# schema_rs232_MAX3232.net
KiCad netlist of a schematic drawn in EAGLE
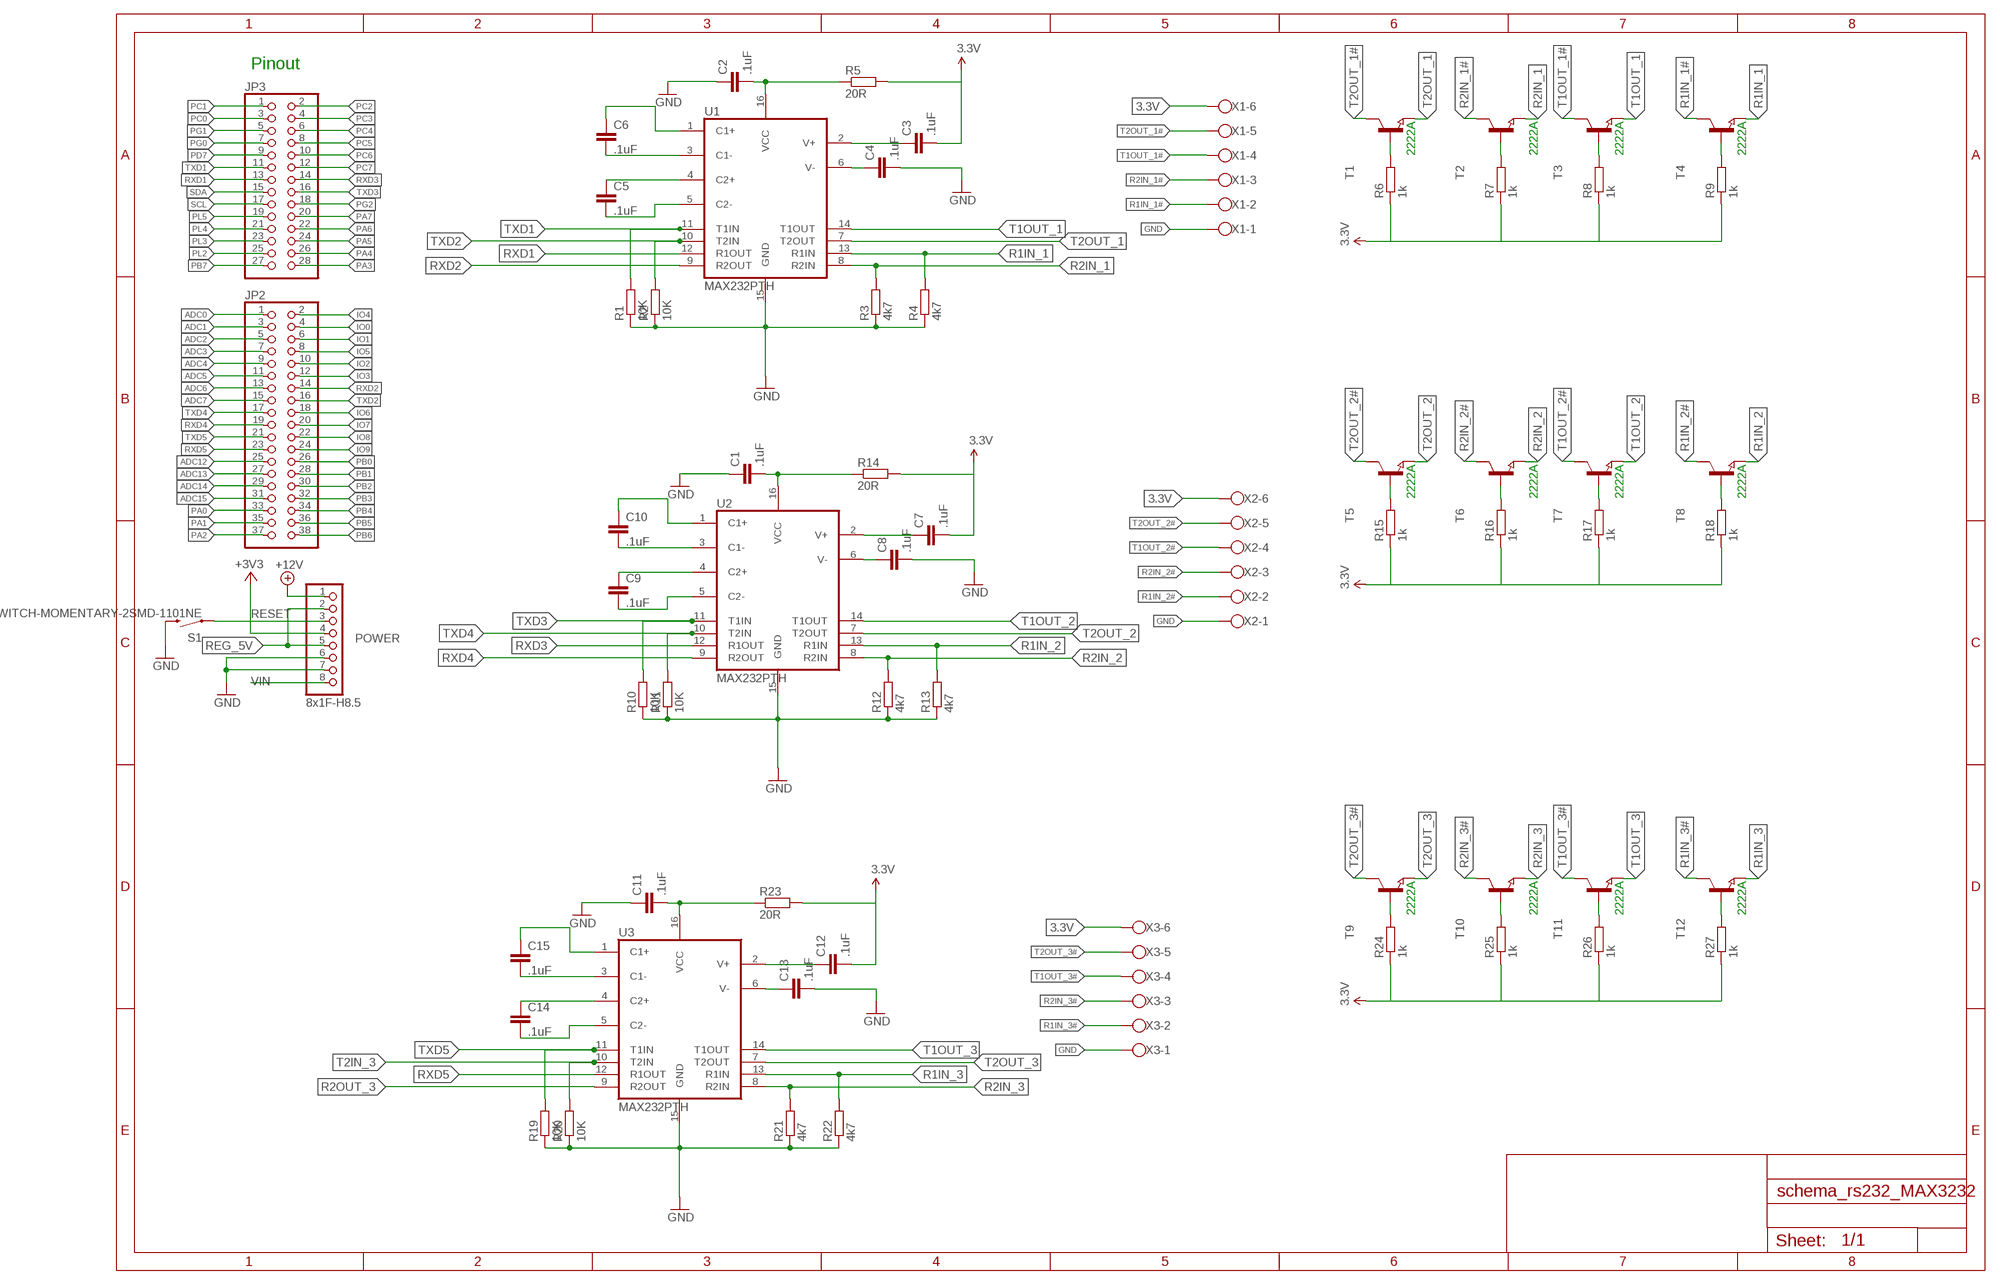
[diagram p0: schematic, sheet 1]

(export (version "E")
  (design (tool "Eeschema 10.0.6"))
  (components
    (comp (ref "C1")
      (value ".1uF")
      (footprint "eagle-import:C0805")
      (libsource (lib "eagle-import") (part "C-EUC0805"))
    )
    (comp (ref "C2")
      (value ".1uF")
      (footprint "eagle-import:C0805")
      (libsource (lib "eagle-import") (part "C-EUC0805"))
    )
    (comp (ref "C3")
      (value ".1uF")
      (footprint "eagle-import:C0805")
      (libsource (lib "eagle-import") (part "C-EUC0805"))
    )
    (comp (ref "C4")
      (value ".1uF")
      (footprint "eagle-import:C0805")
      (libsource (lib "eagle-import") (part "C-EUC0805"))
    )
    (comp (ref "C5")
      (value ".1uF")
      (footprint "eagle-import:C0805")
      (libsource (lib "eagle-import") (part "C-EUC0805"))
    )
    (comp (ref "C6")
      (value ".1uF")
      (footprint "eagle-import:C0805")
      (libsource (lib "eagle-import") (part "C-EUC0805"))
    )
    (comp (ref "C7")
      (value ".1uF")
      (footprint "eagle-import:C0805")
      (libsource (lib "eagle-import") (part "C-EUC0805"))
    )
    (comp (ref "C8")
      (value ".1uF")
      (footprint "eagle-import:C0805")
      (libsource (lib "eagle-import") (part "C-EUC0805"))
    )
    (comp (ref "C9")
      (value ".1uF")
      (footprint "eagle-import:C0805")
      (libsource (lib "eagle-import") (part "C-EUC0805"))
    )
    (comp (ref "C10")
      (value ".1uF")
      (footprint "eagle-import:C0805")
      (libsource (lib "eagle-import") (part "C-EUC0805"))
    )
    (comp (ref "C11")
      (value ".1uF")
      (footprint "eagle-import:C0805")
      (libsource (lib "eagle-import") (part "C-EUC0805"))
    )
    (comp (ref "C12")
      (value ".1uF")
      (footprint "eagle-import:C0805")
      (libsource (lib "eagle-import") (part "C-EUC0805"))
    )
    (comp (ref "C13")
      (value ".1uF")
      (footprint "eagle-import:C0805")
      (libsource (lib "eagle-import") (part "C-EUC0805"))
    )
    (comp (ref "C14")
      (value ".1uF")
      (footprint "eagle-import:C0805")
      (libsource (lib "eagle-import") (part "C-EUC0805"))
    )
    (comp (ref "C15")
      (value ".1uF")
      (footprint "eagle-import:C0805")
      (libsource (lib "eagle-import") (part "C-EUC0805"))
    )
    (comp (ref "JP2")
      (value "PINHD-2X19")
      (footprint "eagle-import:2X19")
      (libsource (lib "eagle-import") (part "PINHD-2X19"))
    )
    (comp (ref "JP3")
      (value "PINHD-2X14")
      (footprint "eagle-import:2X14")
      (libsource (lib "eagle-import") (part "PINHD-2X14"))
    )
    (comp (ref "POWER")
      (value "8x1F-H8.5")
      (footprint "eagle-import:1X08")
      (libsource (lib "eagle-import") (part "PINHD-1X8"))
    )
    (comp (ref "R1")
      (value "10K")
      (footprint "eagle-import:R0805")
      (libsource (lib "eagle-import") (part "R-EU_R0805"))
    )
    (comp (ref "R2")
      (value "10K")
      (footprint "eagle-import:R0805")
      (libsource (lib "eagle-import") (part "R-EU_R0805"))
    )
    (comp (ref "R3")
      (value "4k7")
      (footprint "eagle-import:R0805")
      (libsource (lib "eagle-import") (part "R-EU_R0805"))
    )
    (comp (ref "R4")
      (value "4k7")
      (footprint "eagle-import:R0805")
      (libsource (lib "eagle-import") (part "R-EU_R0805"))
    )
    (comp (ref "R5")
      (value "20R")
      (footprint "eagle-import:R0805")
      (libsource (lib "eagle-import") (part "R-EU_R0805"))
    )
    (comp (ref "R6")
      (value "1k")
      (footprint "eagle-import:R0805")
      (libsource (lib "eagle-import") (part "R-EU_R0805"))
    )
    (comp (ref "R7")
      (value "1k")
      (footprint "eagle-import:R0805")
      (libsource (lib "eagle-import") (part "R-EU_R0805"))
    )
    (comp (ref "R8")
      (value "1k")
      (footprint "eagle-import:R0805")
      (libsource (lib "eagle-import") (part "R-EU_R0805"))
    )
    (comp (ref "R9")
      (value "1k")
      (footprint "eagle-import:R0805")
      (libsource (lib "eagle-import") (part "R-EU_R0805"))
    )
    (comp (ref "R10")
      (value "10K")
      (footprint "eagle-import:R0805")
      (libsource (lib "eagle-import") (part "R-EU_R0805"))
    )
    (comp (ref "R11")
      (value "10K")
      (footprint "eagle-import:R0805")
      (libsource (lib "eagle-import") (part "R-EU_R0805"))
    )
    (comp (ref "R12")
      (value "4k7")
      (footprint "eagle-import:R0805")
      (libsource (lib "eagle-import") (part "R-EU_R0805"))
    )
    (comp (ref "R13")
      (value "4k7")
      (footprint "eagle-import:R0805")
      (libsource (lib "eagle-import") (part "R-EU_R0805"))
    )
    (comp (ref "R14")
      (value "20R")
      (footprint "eagle-import:R0805")
      (libsource (lib "eagle-import") (part "R-EU_R0805"))
    )
    (comp (ref "R15")
      (value "1k")
      (footprint "eagle-import:R0805")
      (libsource (lib "eagle-import") (part "R-EU_R0805"))
    )
    (comp (ref "R16")
      (value "1k")
      (footprint "eagle-import:R0805")
      (libsource (lib "eagle-import") (part "R-EU_R0805"))
    )
    (comp (ref "R17")
      (value "1k")
      (footprint "eagle-import:R0805")
      (libsource (lib "eagle-import") (part "R-EU_R0805"))
    )
    (comp (ref "R18")
      (value "1k")
      (footprint "eagle-import:R0805")
      (libsource (lib "eagle-import") (part "R-EU_R0805"))
    )
    (comp (ref "R19")
      (value "10K")
      (footprint "eagle-import:R0805")
      (libsource (lib "eagle-import") (part "R-EU_R0805"))
    )
    (comp (ref "R20")
      (value "10K")
      (footprint "eagle-import:R0805")
      (libsource (lib "eagle-import") (part "R-EU_R0805"))
    )
    (comp (ref "R21")
      (value "4k7")
      (footprint "eagle-import:R0805")
      (libsource (lib "eagle-import") (part "R-EU_R0805"))
    )
    (comp (ref "R22")
      (value "4k7")
      (footprint "eagle-import:R0805")
      (libsource (lib "eagle-import") (part "R-EU_R0805"))
    )
    (comp (ref "R23")
      (value "20R")
      (footprint "eagle-import:R0805")
      (libsource (lib "eagle-import") (part "R-EU_R0805"))
    )
    (comp (ref "R24")
      (value "1k")
      (footprint "eagle-import:R0805")
      (libsource (lib "eagle-import") (part "R-EU_R0805"))
    )
    (comp (ref "R25")
      (value "1k")
      (footprint "eagle-import:R0805")
      (libsource (lib "eagle-import") (part "R-EU_R0805"))
    )
    (comp (ref "R26")
      (value "1k")
      (footprint "eagle-import:R0805")
      (libsource (lib "eagle-import") (part "R-EU_R0805"))
    )
    (comp (ref "R27")
      (value "1k")
      (footprint "eagle-import:R0805")
      (libsource (lib "eagle-import") (part "R-EU_R0805"))
    )
    (comp (ref "S1")
      (value "SWITCH-MOMENTARY-2SMD-1101NE")
      (footprint "eagle-import:TACTILE-SWITCH-1101NE")
      (libsource (lib "eagle-import") (part "SWITCH-MOMENTARY-2SMD-1101NE"))
    )
    (comp (ref "T1")
      (value "NPN-TRANSISTOR_SOT23")
      (footprint "eagle-import:SOT23")
      (libsource (lib "eagle-import") (part "NPN-TRANSISTOR_SOT23"))
    )
    (comp (ref "T2")
      (value "NPN-TRANSISTOR_SOT23")
      (footprint "eagle-import:SOT23")
      (libsource (lib "eagle-import") (part "NPN-TRANSISTOR_SOT23"))
    )
    (comp (ref "T3")
      (value "NPN-TRANSISTOR_SOT23")
      (footprint "eagle-import:SOT23")
      (libsource (lib "eagle-import") (part "NPN-TRANSISTOR_SOT23"))
    )
    (comp (ref "T4")
      (value "NPN-TRANSISTOR_SOT23")
      (footprint "eagle-import:SOT23")
      (libsource (lib "eagle-import") (part "NPN-TRANSISTOR_SOT23"))
    )
    (comp (ref "T5")
      (value "NPN-TRANSISTOR_SOT23")
      (footprint "eagle-import:SOT23")
      (libsource (lib "eagle-import") (part "NPN-TRANSISTOR_SOT23"))
    )
    (comp (ref "T6")
      (value "NPN-TRANSISTOR_SOT23")
      (footprint "eagle-import:SOT23")
      (libsource (lib "eagle-import") (part "NPN-TRANSISTOR_SOT23"))
    )
    (comp (ref "T7")
      (value "NPN-TRANSISTOR_SOT23")
      (footprint "eagle-import:SOT23")
      (libsource (lib "eagle-import") (part "NPN-TRANSISTOR_SOT23"))
    )
    (comp (ref "T8")
      (value "NPN-TRANSISTOR_SOT23")
      (footprint "eagle-import:SOT23")
      (libsource (lib "eagle-import") (part "NPN-TRANSISTOR_SOT23"))
    )
    (comp (ref "T9")
      (value "NPN-TRANSISTOR_SOT23")
      (footprint "eagle-import:SOT23")
      (libsource (lib "eagle-import") (part "NPN-TRANSISTOR_SOT23"))
    )
    (comp (ref "T10")
      (value "NPN-TRANSISTOR_SOT23")
      (footprint "eagle-import:SOT23")
      (libsource (lib "eagle-import") (part "NPN-TRANSISTOR_SOT23"))
    )
    (comp (ref "T11")
      (value "NPN-TRANSISTOR_SOT23")
      (footprint "eagle-import:SOT23")
      (libsource (lib "eagle-import") (part "NPN-TRANSISTOR_SOT23"))
    )
    (comp (ref "T12")
      (value "NPN-TRANSISTOR_SOT23")
      (footprint "eagle-import:SOT23")
      (libsource (lib "eagle-import") (part "NPN-TRANSISTOR_SOT23"))
    )
    (comp (ref "U1")
      (value "MAX232PTH")
      (footprint "eagle-import:DIL16")
      (libsource (lib "eagle-import") (part "MAX232PTH"))
    )
    (comp (ref "U2")
      (value "MAX232PTH")
      (footprint "eagle-import:DIL16")
      (libsource (lib "eagle-import") (part "MAX232PTH"))
    )
    (comp (ref "U3")
      (value "MAX232PTH")
      (footprint "eagle-import:DIL16")
      (libsource (lib "eagle-import") (part "MAX232PTH"))
    )
    (comp (ref "X1")
      (value "W237-6")
      (footprint "eagle-import:W237-6")
      (libsource (lib "eagle-import") (part "W237-6"))
    )
    (comp (ref "X2")
      (value "W237-6")
      (footprint "eagle-import:W237-6")
      (libsource (lib "eagle-import") (part "W237-6"))
    )
    (comp (ref "X3")
      (value "W237-6")
      (footprint "eagle-import:W237-6")
      (libsource (lib "eagle-import") (part "W237-6"))
    )
  )
  (nets
    (net (code "1") (name "+12V") (class "Default")
      (node (ref "POWER") (pin "1") (pinfunction "1_1") (pintype "passive"))
    )
    (net (code "2") (name "/RESET") (class "Default")
      (node (ref "POWER") (pin "3") (pinfunction "3_3") (pintype "passive"))
      (node (ref "S1") (pin "1") (pinfunction "1_1") (pintype "passive"))
    )
    (net (code "3") (name "/VIN") (class "Default")
      (node (ref "POWER") (pin "8") (pinfunction "8_8") (pintype "passive"))
    )
    (net (code "4") (name "3.3V") (class "Default")
      (node (ref "C12") (pin "2") (pinfunction "2_2") (pintype "passive"))
      (node (ref "C3") (pin "2") (pinfunction "2_2") (pintype "passive"))
      (node (ref "C7") (pin "2") (pinfunction "2_2") (pintype "passive"))
      (node (ref "POWER") (pin "4") (pinfunction "4_4") (pintype "passive"))
      (node (ref "R14") (pin "2") (pinfunction "2_2") (pintype "passive"))
      (node (ref "R15") (pin "1") (pinfunction "1_1") (pintype "passive"))
      (node (ref "R16") (pin "1") (pinfunction "1_1") (pintype "passive"))
      (node (ref "R17") (pin "1") (pinfunction "1_1") (pintype "passive"))
      (node (ref "R18") (pin "1") (pinfunction "1_1") (pintype "passive"))
      (node (ref "R23") (pin "2") (pinfunction "2_2") (pintype "passive"))
      (node (ref "R24") (pin "1") (pinfunction "1_1") (pintype "passive"))
      (node (ref "R25") (pin "1") (pinfunction "1_1") (pintype "passive"))
      (node (ref "R26") (pin "1") (pinfunction "1_1") (pintype "passive"))
      (node (ref "R27") (pin "1") (pinfunction "1_1") (pintype "passive"))
      (node (ref "R5") (pin "2") (pinfunction "2_2") (pintype "passive"))
      (node (ref "R6") (pin "1") (pinfunction "1_1") (pintype "passive"))
      (node (ref "R7") (pin "1") (pinfunction "1_1") (pintype "passive"))
      (node (ref "R8") (pin "1") (pinfunction "1_1") (pintype "passive"))
      (node (ref "R9") (pin "1") (pinfunction "1_1") (pintype "passive"))
      (node (ref "X1") (pin "6") (pinfunction "KL_6") (pintype "passive"))
      (node (ref "X2") (pin "6") (pinfunction "KL_6") (pintype "passive"))
      (node (ref "X3") (pin "6") (pinfunction "KL_6") (pintype "passive"))
    )
    (net (code "5") (name "ADC0") (class "Default")
      (node (ref "JP2") (pin "1") (pinfunction "1_1") (pintype "passive"))
    )
    (net (code "6") (name "ADC1") (class "Default")
      (node (ref "JP2") (pin "3") (pinfunction "3_3") (pintype "passive"))
    )
    (net (code "7") (name "ADC2") (class "Default")
      (node (ref "JP2") (pin "5") (pinfunction "5_5") (pintype "passive"))
    )
    (net (code "8") (name "ADC3") (class "Default")
      (node (ref "JP2") (pin "7") (pinfunction "7_7") (pintype "passive"))
    )
    (net (code "9") (name "ADC4") (class "Default")
      (node (ref "JP2") (pin "9") (pinfunction "9_9") (pintype "passive"))
    )
    (net (code "10") (name "ADC5") (class "Default")
      (node (ref "JP2") (pin "11") (pinfunction "11_11") (pintype "passive"))
    )
    (net (code "11") (name "ADC6") (class "Default")
      (node (ref "JP2") (pin "13") (pinfunction "13_13") (pintype "passive"))
    )
    (net (code "12") (name "ADC7") (class "Default")
      (node (ref "JP2") (pin "15") (pinfunction "15_15") (pintype "passive"))
    )
    (net (code "13") (name "ADC12") (class "Default")
      (node (ref "JP2") (pin "25") (pinfunction "25_25") (pintype "passive"))
    )
    (net (code "14") (name "ADC13") (class "Default")
      (node (ref "JP2") (pin "27") (pinfunction "27_27") (pintype "passive"))
    )
    (net (code "15") (name "ADC14") (class "Default")
      (node (ref "JP2") (pin "29") (pinfunction "29_29") (pintype "passive"))
    )
    (net (code "16") (name "ADC15") (class "Default")
      (node (ref "JP2") (pin "31") (pinfunction "31_31") (pintype "passive"))
    )
    (net (code "17") (name "GND") (class "Default")
      (node (ref "C1") (pin "1") (pinfunction "1_1") (pintype "passive"))
      (node (ref "C11") (pin "1") (pinfunction "1_1") (pintype "passive"))
      (node (ref "C13") (pin "2") (pinfunction "2_2") (pintype "passive"))
      (node (ref "C2") (pin "1") (pinfunction "1_1") (pintype "passive"))
      (node (ref "C4") (pin "2") (pinfunction "2_2") (pintype "passive"))
      (node (ref "C8") (pin "2") (pinfunction "2_2") (pintype "passive"))
      (node (ref "POWER") (pin "6") (pinfunction "6_6") (pintype "passive"))
      (node (ref "POWER") (pin "7") (pinfunction "7_7") (pintype "passive"))
      (node (ref "R1") (pin "1") (pinfunction "1_1") (pintype "passive"))
      (node (ref "R10") (pin "1") (pinfunction "1_1") (pintype "passive"))
      (node (ref "R11") (pin "1") (pinfunction "1_1") (pintype "passive"))
      (node (ref "R12") (pin "1") (pinfunction "1_1") (pintype "passive"))
      (node (ref "R13") (pin "1") (pinfunction "1_1") (pintype "passive"))
      (node (ref "R19") (pin "1") (pinfunction "1_1") (pintype "passive"))
      (node (ref "R2") (pin "1") (pinfunction "1_1") (pintype "passive"))
      (node (ref "R20") (pin "1") (pinfunction "1_1") (pintype "passive"))
      (node (ref "R21") (pin "1") (pinfunction "1_1") (pintype "passive"))
      (node (ref "R22") (pin "1") (pinfunction "1_1") (pintype "passive"))
      (node (ref "R3") (pin "1") (pinfunction "1_1") (pintype "passive"))
      (node (ref "R4") (pin "1") (pinfunction "1_1") (pintype "passive"))
      (node (ref "S1") (pin "2") (pinfunction "2_2") (pintype "passive"))
      (node (ref "U1") (pin "15") (pinfunction "GND_15") (pintype "bidirectional"))
      (node (ref "U2") (pin "15") (pinfunction "GND_15") (pintype "bidirectional"))
      (node (ref "U3") (pin "15") (pinfunction "GND_15") (pintype "bidirectional"))
      (node (ref "X1") (pin "1") (pinfunction "KL_1") (pintype "passive"))
      (node (ref "X2") (pin "1") (pinfunction "KL_1") (pintype "passive"))
      (node (ref "X3") (pin "1") (pinfunction "KL_1") (pintype "passive"))
    )
    (net (code "18") (name "IO0") (class "Default")
      (node (ref "JP2") (pin "4") (pinfunction "4_4") (pintype "passive"))
    )
    (net (code "19") (name "IO1") (class "Default")
      (node (ref "JP2") (pin "6") (pinfunction "6_6") (pintype "passive"))
    )
    (net (code "20") (name "IO2") (class "Default")
      (node (ref "JP2") (pin "10") (pinfunction "10_10") (pintype "passive"))
    )
    (net (code "21") (name "IO3") (class "Default")
      (node (ref "JP2") (pin "12") (pinfunction "12_12") (pintype "passive"))
    )
    (net (code "22") (name "IO4") (class "Default")
      (node (ref "JP2") (pin "2") (pinfunction "2_2") (pintype "passive"))
    )
    (net (code "23") (name "IO5") (class "Default")
      (node (ref "JP2") (pin "8") (pinfunction "8_8") (pintype "passive"))
    )
    (net (code "24") (name "IO6") (class "Default")
      (node (ref "JP2") (pin "18") (pinfunction "18_18") (pintype "passive"))
    )
    (net (code "25") (name "IO7") (class "Default")
      (node (ref "JP2") (pin "20") (pinfunction "20_20") (pintype "passive"))
    )
    (net (code "26") (name "IO8") (class "Default")
      (node (ref "JP2") (pin "22") (pinfunction "22_22") (pintype "passive"))
    )
    (net (code "27") (name "IO9") (class "Default")
      (node (ref "JP2") (pin "24") (pinfunction "24_24") (pintype "passive"))
    )
    (net (code "28") (name "Net-(T1-B)") (class "Default")
      (node (ref "R6") (pin "2") (pinfunction "2_2") (pintype "passive"))
      (node (ref "T1") (pin "1") (pinfunction "B_1") (pintype "passive"))
    )
    (net (code "29") (name "Net-(T2-B)") (class "Default")
      (node (ref "R7") (pin "2") (pinfunction "2_2") (pintype "passive"))
      (node (ref "T2") (pin "1") (pinfunction "B_1") (pintype "passive"))
    )
    (net (code "30") (name "Net-(T3-B)") (class "Default")
      (node (ref "R8") (pin "2") (pinfunction "2_2") (pintype "passive"))
      (node (ref "T3") (pin "1") (pinfunction "B_1") (pintype "passive"))
    )
    (net (code "31") (name "Net-(T4-B)") (class "Default")
      (node (ref "R9") (pin "2") (pinfunction "2_2") (pintype "passive"))
      (node (ref "T4") (pin "1") (pinfunction "B_1") (pintype "passive"))
    )
    (net (code "32") (name "Net-(T5-B)") (class "Default")
      (node (ref "R15") (pin "2") (pinfunction "2_2") (pintype "passive"))
      (node (ref "T5") (pin "1") (pinfunction "B_1") (pintype "passive"))
    )
    (net (code "33") (name "Net-(T6-B)") (class "Default")
      (node (ref "R16") (pin "2") (pinfunction "2_2") (pintype "passive"))
      (node (ref "T6") (pin "1") (pinfunction "B_1") (pintype "passive"))
    )
    (net (code "34") (name "Net-(T7-B)") (class "Default")
      (node (ref "R17") (pin "2") (pinfunction "2_2") (pintype "passive"))
      (node (ref "T7") (pin "1") (pinfunction "B_1") (pintype "passive"))
    )
    (net (code "35") (name "Net-(T8-B)") (class "Default")
      (node (ref "R18") (pin "2") (pinfunction "2_2") (pintype "passive"))
      (node (ref "T8") (pin "1") (pinfunction "B_1") (pintype "passive"))
    )
    (net (code "36") (name "Net-(T9-B)") (class "Default")
      (node (ref "R24") (pin "2") (pinfunction "2_2") (pintype "passive"))
      (node (ref "T9") (pin "1") (pinfunction "B_1") (pintype "passive"))
    )
    (net (code "37") (name "Net-(T10-B)") (class "Default")
      (node (ref "R25") (pin "2") (pinfunction "2_2") (pintype "passive"))
      (node (ref "T10") (pin "1") (pinfunction "B_1") (pintype "passive"))
    )
    (net (code "38") (name "Net-(T11-B)") (class "Default")
      (node (ref "R26") (pin "2") (pinfunction "2_2") (pintype "passive"))
      (node (ref "T11") (pin "1") (pinfunction "B_1") (pintype "passive"))
    )
    (net (code "39") (name "Net-(T12-B)") (class "Default")
      (node (ref "R27") (pin "2") (pinfunction "2_2") (pintype "passive"))
      (node (ref "T12") (pin "1") (pinfunction "B_1") (pintype "passive"))
    )
    (net (code "40") (name "Net-(U1-C1+)") (class "Default")
      (node (ref "C6") (pin "1") (pinfunction "1_1") (pintype "passive"))
      (node (ref "U1") (pin "1") (pinfunction "C1+_1") (pintype "bidirectional"))
    )
    (net (code "41") (name "Net-(U1-C1-)") (class "Default")
      (node (ref "C6") (pin "2") (pinfunction "2_2") (pintype "passive"))
      (node (ref "U1") (pin "3") (pinfunction "C1-_3") (pintype "bidirectional"))
    )
    (net (code "42") (name "Net-(U1-C2+)") (class "Default")
      (node (ref "C5") (pin "1") (pinfunction "1_1") (pintype "passive"))
      (node (ref "U1") (pin "4") (pinfunction "C2+_4") (pintype "bidirectional"))
    )
    (net (code "43") (name "Net-(U1-C2-)") (class "Default")
      (node (ref "C5") (pin "2") (pinfunction "2_2") (pintype "passive"))
      (node (ref "U1") (pin "5") (pinfunction "C2-_5") (pintype "bidirectional"))
    )
    (net (code "44") (name "Net-(U1-V+)") (class "Default")
      (node (ref "C3") (pin "1") (pinfunction "1_1") (pintype "passive"))
      (node (ref "U1") (pin "2") (pinfunction "V+_2") (pintype "bidirectional"))
    )
    (net (code "45") (name "Net-(U1-V-)") (class "Default")
      (node (ref "C4") (pin "1") (pinfunction "1_1") (pintype "passive"))
      (node (ref "U1") (pin "6") (pinfunction "V-_6") (pintype "bidirectional"))
    )
    (net (code "46") (name "Net-(U1-VCC)") (class "Default")
      (node (ref "C2") (pin "2") (pinfunction "2_2") (pintype "passive"))
      (node (ref "R5") (pin "1") (pinfunction "1_1") (pintype "passive"))
      (node (ref "U1") (pin "16") (pinfunction "VCC_16") (pintype "bidirectional"))
    )
    (net (code "47") (name "Net-(U2-C1+)") (class "Default")
      (node (ref "C10") (pin "1") (pinfunction "1_1") (pintype "passive"))
      (node (ref "U2") (pin "1") (pinfunction "C1+_1") (pintype "bidirectional"))
    )
    (net (code "48") (name "Net-(U2-C1-)") (class "Default")
      (node (ref "C10") (pin "2") (pinfunction "2_2") (pintype "passive"))
      (node (ref "U2") (pin "3") (pinfunction "C1-_3") (pintype "bidirectional"))
    )
    (net (code "49") (name "Net-(U2-C2+)") (class "Default")
      (node (ref "C9") (pin "1") (pinfunction "1_1") (pintype "passive"))
      (node (ref "U2") (pin "4") (pinfunction "C2+_4") (pintype "bidirectional"))
    )
    (net (code "50") (name "Net-(U2-C2-)") (class "Default")
      (node (ref "C9") (pin "2") (pinfunction "2_2") (pintype "passive"))
      (node (ref "U2") (pin "5") (pinfunction "C2-_5") (pintype "bidirectional"))
    )
    (net (code "51") (name "Net-(U2-V+)") (class "Default")
      (node (ref "C7") (pin "1") (pinfunction "1_1") (pintype "passive"))
      (node (ref "U2") (pin "2") (pinfunction "V+_2") (pintype "bidirectional"))
    )
    (net (code "52") (name "Net-(U2-V-)") (class "Default")
      (node (ref "C8") (pin "1") (pinfunction "1_1") (pintype "passive"))
      (node (ref "U2") (pin "6") (pinfunction "V-_6") (pintype "bidirectional"))
    )
    (net (code "53") (name "Net-(U2-VCC)") (class "Default")
      (node (ref "C1") (pin "2") (pinfunction "2_2") (pintype "passive"))
      (node (ref "R14") (pin "1") (pinfunction "1_1") (pintype "passive"))
      (node (ref "U2") (pin "16") (pinfunction "VCC_16") (pintype "bidirectional"))
    )
    (net (code "54") (name "Net-(U3-C1+)") (class "Default")
      (node (ref "C15") (pin "1") (pinfunction "1_1") (pintype "passive"))
      (node (ref "U3") (pin "1") (pinfunction "C1+_1") (pintype "bidirectional"))
    )
    (net (code "55") (name "Net-(U3-C1-)") (class "Default")
      (node (ref "C15") (pin "2") (pinfunction "2_2") (pintype "passive"))
      (node (ref "U3") (pin "3") (pinfunction "C1-_3") (pintype "bidirectional"))
    )
    (net (code "56") (name "Net-(U3-C2+)") (class "Default")
      (node (ref "C14") (pin "1") (pinfunction "1_1") (pintype "passive"))
      (node (ref "U3") (pin "4") (pinfunction "C2+_4") (pintype "bidirectional"))
    )
    (net (code "57") (name "Net-(U3-C2-)") (class "Default")
      (node (ref "C14") (pin "2") (pinfunction "2_2") (pintype "passive"))
      (node (ref "U3") (pin "5") (pinfunction "C2-_5") (pintype "bidirectional"))
    )
    (net (code "58") (name "Net-(U3-V+)") (class "Default")
      (node (ref "C12") (pin "1") (pinfunction "1_1") (pintype "passive"))
      (node (ref "U3") (pin "2") (pinfunction "V+_2") (pintype "bidirectional"))
    )
    (net (code "59") (name "Net-(U3-V-)") (class "Default")
      (node (ref "C13") (pin "1") (pinfunction "1_1") (pintype "passive"))
      (node (ref "U3") (pin "6") (pinfunction "V-_6") (pintype "bidirectional"))
    )
    (net (code "60") (name "Net-(U3-VCC)") (class "Default")
      (node (ref "C11") (pin "2") (pinfunction "2_2") (pintype "passive"))
      (node (ref "R23") (pin "1") (pinfunction "1_1") (pintype "passive"))
      (node (ref "U3") (pin "16") (pinfunction "VCC_16") (pintype "bidirectional"))
    )
    (net (code "61") (name "PA0") (class "Default")
      (node (ref "JP2") (pin "33") (pinfunction "33_33") (pintype "passive"))
    )
    (net (code "62") (name "PA1") (class "Default")
      (node (ref "JP2") (pin "35") (pinfunction "35_35") (pintype "passive"))
    )
    (net (code "63") (name "PA2") (class "Default")
      (node (ref "JP2") (pin "37") (pinfunction "37_37") (pintype "passive"))
    )
    (net (code "64") (name "PA3") (class "Default")
      (node (ref "JP3") (pin "28") (pinfunction "28_28") (pintype "passive"))
    )
    (net (code "65") (name "PA4") (class "Default")
      (node (ref "JP3") (pin "26") (pinfunction "26_26") (pintype "passive"))
    )
    (net (code "66") (name "PA5") (class "Default")
      (node (ref "JP3") (pin "24") (pinfunction "24_24") (pintype "passive"))
    )
    (net (code "67") (name "PA6") (class "Default")
      (node (ref "JP3") (pin "22") (pinfunction "22_22") (pintype "passive"))
    )
    (net (code "68") (name "PA7") (class "Default")
      (node (ref "JP3") (pin "20") (pinfunction "20_20") (pintype "passive"))
    )
    (net (code "69") (name "PB0") (class "Default")
      (node (ref "JP2") (pin "26") (pinfunction "26_26") (pintype "passive"))
    )
    (net (code "70") (name "PB1") (class "Default")
      (node (ref "JP2") (pin "28") (pinfunction "28_28") (pintype "passive"))
    )
    (net (code "71") (name "PB2") (class "Default")
      (node (ref "JP2") (pin "30") (pinfunction "30_30") (pintype "passive"))
    )
    (net (code "72") (name "PB3") (class "Default")
      (node (ref "JP2") (pin "32") (pinfunction "32_32") (pintype "passive"))
    )
    (net (code "73") (name "PB4") (class "Default")
      (node (ref "JP2") (pin "34") (pinfunction "34_34") (pintype "passive"))
    )
    (net (code "74") (name "PB5") (class "Default")
      (node (ref "JP2") (pin "36") (pinfunction "36_36") (pintype "passive"))
    )
    (net (code "75") (name "PB6") (class "Default")
      (node (ref "JP2") (pin "38") (pinfunction "38_38") (pintype "passive"))
    )
    (net (code "76") (name "PB7") (class "Default")
      (node (ref "JP3") (pin "27") (pinfunction "27_27") (pintype "passive"))
    )
    (net (code "77") (name "PC0") (class "Default")
      (node (ref "JP3") (pin "3") (pinfunction "3_3") (pintype "passive"))
    )
    (net (code "78") (name "PC1") (class "Default")
      (node (ref "JP3") (pin "1") (pinfunction "1_1") (pintype "passive"))
    )
    (net (code "79") (name "PC2") (class "Default")
      (node (ref "JP3") (pin "2") (pinfunction "2_2") (pintype "passive"))
    )
    (net (code "80") (name "PC3") (class "Default")
      (node (ref "JP3") (pin "4") (pinfunction "4_4") (pintype "passive"))
    )
    (net (code "81") (name "PC4") (class "Default")
      (node (ref "JP3") (pin "6") (pinfunction "6_6") (pintype "passive"))
    )
    (net (code "82") (name "PC5") (class "Default")
      (node (ref "JP3") (pin "8") (pinfunction "8_8") (pintype "passive"))
    )
    (net (code "83") (name "PC6") (class "Default")
      (node (ref "JP3") (pin "10") (pinfunction "10_10") (pintype "passive"))
    )
    (net (code "84") (name "PC7") (class "Default")
      (node (ref "JP3") (pin "12") (pinfunction "12_12") (pintype "passive"))
    )
    (net (code "85") (name "PD7") (class "Default")
      (node (ref "JP3") (pin "9") (pinfunction "9_9") (pintype "passive"))
    )
    (net (code "86") (name "PG0") (class "Default")
      (node (ref "JP3") (pin "7") (pinfunction "7_7") (pintype "passive"))
    )
    (net (code "87") (name "PG1") (class "Default")
      (node (ref "JP3") (pin "5") (pinfunction "5_5") (pintype "passive"))
    )
    (net (code "88") (name "PG2") (class "Default")
      (node (ref "JP3") (pin "18") (pinfunction "18_18") (pintype "passive"))
    )
    (net (code "89") (name "PL2") (class "Default")
      (node (ref "JP3") (pin "25") (pinfunction "25_25") (pintype "passive"))
    )
    (net (code "90") (name "PL3") (class "Default")
      (node (ref "JP3") (pin "23") (pinfunction "23_23") (pintype "passive"))
    )
    (net (code "91") (name "PL4") (class "Default")
      (node (ref "JP3") (pin "21") (pinfunction "21_21") (pintype "passive"))
    )
    (net (code "92") (name "PL5") (class "Default")
      (node (ref "JP3") (pin "19") (pinfunction "19_19") (pintype "passive"))
    )
    (net (code "93") (name "R1IN_1") (class "Default")
      (node (ref "R4") (pin "2") (pinfunction "2_2") (pintype "passive"))
      (node (ref "T4") (pin "2") (pinfunction "E_2") (pintype "passive"))
      (node (ref "U1") (pin "13") (pinfunction "R1IN_13") (pintype "input"))
    )
    (net (code "94") (name "R1IN_1#") (class "Default")
      (node (ref "T4") (pin "3") (pinfunction "C_3") (pintype "passive"))
      (node (ref "X1") (pin "2") (pinfunction "KL_2") (pintype "passive"))
    )
    (net (code "95") (name "R1IN_2") (class "Default")
      (node (ref "R13") (pin "2") (pinfunction "2_2") (pintype "passive"))
      (node (ref "T8") (pin "2") (pinfunction "E_2") (pintype "passive"))
      (node (ref "U2") (pin "13") (pinfunction "R1IN_13") (pintype "input"))
    )
    (net (code "96") (name "R1IN_2#") (class "Default")
      (node (ref "T8") (pin "3") (pinfunction "C_3") (pintype "passive"))
      (node (ref "X2") (pin "2") (pinfunction "KL_2") (pintype "passive"))
    )
    (net (code "97") (name "R1IN_3") (class "Default")
      (node (ref "R22") (pin "2") (pinfunction "2_2") (pintype "passive"))
      (node (ref "T12") (pin "2") (pinfunction "E_2") (pintype "passive"))
      (node (ref "U3") (pin "13") (pinfunction "R1IN_13") (pintype "input"))
    )
    (net (code "98") (name "R1IN_3#") (class "Default")
      (node (ref "T12") (pin "3") (pinfunction "C_3") (pintype "passive"))
      (node (ref "X3") (pin "2") (pinfunction "KL_2") (pintype "passive"))
    )
    (net (code "99") (name "R2IN_1") (class "Default")
      (node (ref "R3") (pin "2") (pinfunction "2_2") (pintype "passive"))
      (node (ref "T2") (pin "2") (pinfunction "E_2") (pintype "passive"))
      (node (ref "U1") (pin "8") (pinfunction "R2IN_8") (pintype "input"))
    )
    (net (code "100") (name "R2IN_1#") (class "Default")
      (node (ref "T2") (pin "3") (pinfunction "C_3") (pintype "passive"))
      (node (ref "X1") (pin "3") (pinfunction "KL_3") (pintype "passive"))
    )
    (net (code "101") (name "R2IN_2") (class "Default")
      (node (ref "R12") (pin "2") (pinfunction "2_2") (pintype "passive"))
      (node (ref "T6") (pin "2") (pinfunction "E_2") (pintype "passive"))
      (node (ref "U2") (pin "8") (pinfunction "R2IN_8") (pintype "input"))
    )
    (net (code "102") (name "R2IN_2#") (class "Default")
      (node (ref "T6") (pin "3") (pinfunction "C_3") (pintype "passive"))
      (node (ref "X2") (pin "3") (pinfunction "KL_3") (pintype "passive"))
    )
    (net (code "103") (name "R2IN_3") (class "Default")
      (node (ref "R21") (pin "2") (pinfunction "2_2") (pintype "passive"))
      (node (ref "T10") (pin "2") (pinfunction "E_2") (pintype "passive"))
      (node (ref "U3") (pin "8") (pinfunction "R2IN_8") (pintype "input"))
    )
    (net (code "104") (name "R2IN_3#") (class "Default")
      (node (ref "T10") (pin "3") (pinfunction "C_3") (pintype "passive"))
      (node (ref "X3") (pin "3") (pinfunction "KL_3") (pintype "passive"))
    )
    (net (code "105") (name "R2OUT_3") (class "Default")
      (node (ref "U3") (pin "9") (pinfunction "R2OUT_9") (pintype "output"))
    )
    (net (code "106") (name "REG_5V") (class "Default")
      (node (ref "POWER") (pin "2") (pinfunction "2_2") (pintype "passive"))
      (node (ref "POWER") (pin "5") (pinfunction "5_5") (pintype "passive"))
    )
    (net (code "107") (name "RXD1") (class "Default")
      (node (ref "JP3") (pin "13") (pinfunction "13_13") (pintype "passive"))
      (node (ref "U1") (pin "12") (pinfunction "R1OUT_12") (pintype "output"))
    )
    (net (code "108") (name "RXD2") (class "Default")
      (node (ref "JP2") (pin "14") (pinfunction "14_14") (pintype "passive"))
      (node (ref "U1") (pin "9") (pinfunction "R2OUT_9") (pintype "output"))
    )
    (net (code "109") (name "RXD3") (class "Default")
      (node (ref "JP3") (pin "14") (pinfunction "14_14") (pintype "passive"))
      (node (ref "U2") (pin "12") (pinfunction "R1OUT_12") (pintype "output"))
    )
    (net (code "110") (name "RXD4") (class "Default")
      (node (ref "JP2") (pin "19") (pinfunction "19_19") (pintype "passive"))
      (node (ref "U2") (pin "9") (pinfunction "R2OUT_9") (pintype "output"))
    )
    (net (code "111") (name "RXD5") (class "Default")
      (node (ref "JP2") (pin "23") (pinfunction "23_23") (pintype "passive"))
      (node (ref "U3") (pin "12") (pinfunction "R1OUT_12") (pintype "output"))
    )
    (net (code "112") (name "SCL") (class "Default")
      (node (ref "JP3") (pin "17") (pinfunction "17_17") (pintype "passive"))
    )
    (net (code "113") (name "SDA") (class "Default")
      (node (ref "JP3") (pin "15") (pinfunction "15_15") (pintype "passive"))
    )
    (net (code "114") (name "T1OUT_1") (class "Default")
      (node (ref "T3") (pin "2") (pinfunction "E_2") (pintype "passive"))
      (node (ref "U1") (pin "14") (pinfunction "T1OUT_14") (pintype "output"))
    )
    (net (code "115") (name "T1OUT_1#") (class "Default")
      (node (ref "T3") (pin "3") (pinfunction "C_3") (pintype "passive"))
      (node (ref "X1") (pin "4") (pinfunction "KL_4") (pintype "passive"))
    )
    (net (code "116") (name "T1OUT_2") (class "Default")
      (node (ref "T7") (pin "2") (pinfunction "E_2") (pintype "passive"))
      (node (ref "U2") (pin "14") (pinfunction "T1OUT_14") (pintype "output"))
    )
    (net (code "117") (name "T1OUT_2#") (class "Default")
      (node (ref "T7") (pin "3") (pinfunction "C_3") (pintype "passive"))
      (node (ref "X2") (pin "4") (pinfunction "KL_4") (pintype "passive"))
    )
    (net (code "118") (name "T1OUT_3") (class "Default")
      (node (ref "T11") (pin "2") (pinfunction "E_2") (pintype "passive"))
      (node (ref "U3") (pin "14") (pinfunction "T1OUT_14") (pintype "output"))
    )
    (net (code "119") (name "T1OUT_3#") (class "Default")
      (node (ref "T11") (pin "3") (pinfunction "C_3") (pintype "passive"))
      (node (ref "X3") (pin "4") (pinfunction "KL_4") (pintype "passive"))
    )
    (net (code "120") (name "T2IN_3") (class "Default")
      (node (ref "R20") (pin "2") (pinfunction "2_2") (pintype "passive"))
      (node (ref "U3") (pin "10") (pinfunction "T2IN_10") (pintype "input"))
    )
    (net (code "121") (name "T2OUT_1") (class "Default")
      (node (ref "T1") (pin "2") (pinfunction "E_2") (pintype "passive"))
      (node (ref "U1") (pin "7") (pinfunction "T2OUT_7") (pintype "output"))
    )
    (net (code "122") (name "T2OUT_1#") (class "Default")
      (node (ref "T1") (pin "3") (pinfunction "C_3") (pintype "passive"))
      (node (ref "X1") (pin "5") (pinfunction "KL_5") (pintype "passive"))
    )
    (net (code "123") (name "T2OUT_2") (class "Default")
      (node (ref "T5") (pin "2") (pinfunction "E_2") (pintype "passive"))
      (node (ref "U2") (pin "7") (pinfunction "T2OUT_7") (pintype "output"))
    )
    (net (code "124") (name "T2OUT_2#") (class "Default")
      (node (ref "T5") (pin "3") (pinfunction "C_3") (pintype "passive"))
      (node (ref "X2") (pin "5") (pinfunction "KL_5") (pintype "passive"))
    )
    (net (code "125") (name "T2OUT_3") (class "Default")
      (node (ref "T9") (pin "2") (pinfunction "E_2") (pintype "passive"))
      (node (ref "U3") (pin "7") (pinfunction "T2OUT_7") (pintype "output"))
    )
    (net (code "126") (name "T2OUT_3#") (class "Default")
      (node (ref "T9") (pin "3") (pinfunction "C_3") (pintype "passive"))
      (node (ref "X3") (pin "5") (pinfunction "KL_5") (pintype "passive"))
    )
    (net (code "127") (name "TXD1") (class "Default")
      (node (ref "JP3") (pin "11") (pinfunction "11_11") (pintype "passive"))
      (node (ref "R1") (pin "2") (pinfunction "2_2") (pintype "passive"))
      (node (ref "U1") (pin "11") (pinfunction "T1IN_11") (pintype "input"))
    )
    (net (code "128") (name "TXD2") (class "Default")
      (node (ref "JP2") (pin "16") (pinfunction "16_16") (pintype "passive"))
      (node (ref "R2") (pin "2") (pinfunction "2_2") (pintype "passive"))
      (node (ref "U1") (pin "10") (pinfunction "T2IN_10") (pintype "input"))
    )
    (net (code "129") (name "TXD3") (class "Default")
      (node (ref "JP3") (pin "16") (pinfunction "16_16") (pintype "passive"))
      (node (ref "R10") (pin "2") (pinfunction "2_2") (pintype "passive"))
      (node (ref "U2") (pin "11") (pinfunction "T1IN_11") (pintype "input"))
    )
    (net (code "130") (name "TXD4") (class "Default")
      (node (ref "JP2") (pin "17") (pinfunction "17_17") (pintype "passive"))
      (node (ref "R11") (pin "2") (pinfunction "2_2") (pintype "passive"))
      (node (ref "U2") (pin "10") (pinfunction "T2IN_10") (pintype "input"))
    )
    (net (code "131") (name "TXD5") (class "Default")
      (node (ref "JP2") (pin "21") (pinfunction "21_21") (pintype "passive"))
      (node (ref "R19") (pin "2") (pinfunction "2_2") (pintype "passive"))
      (node (ref "U3") (pin "11") (pinfunction "T1IN_11") (pintype "input"))
    )
  )
)
